# V1.net
KiCad netlist of a schematic drawn in EAGLE
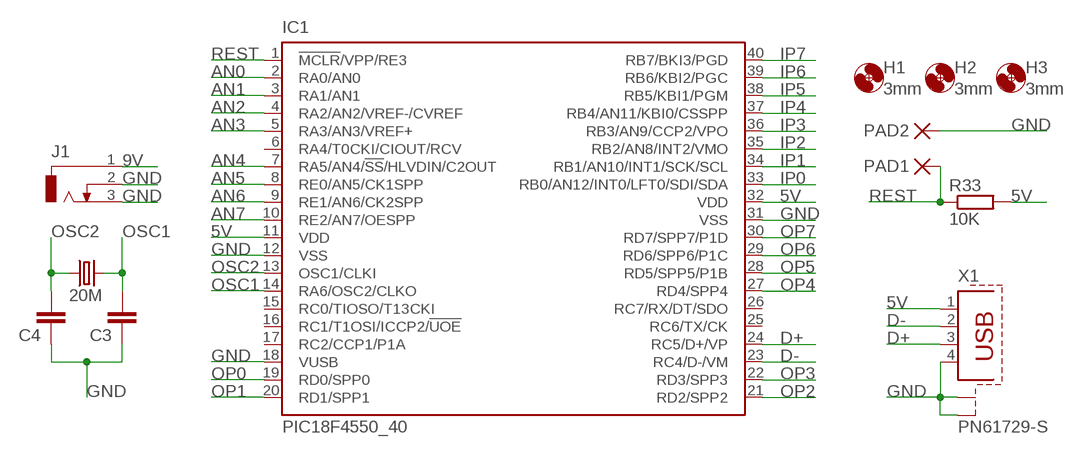
[diagram p0: schematic, sheet 1]
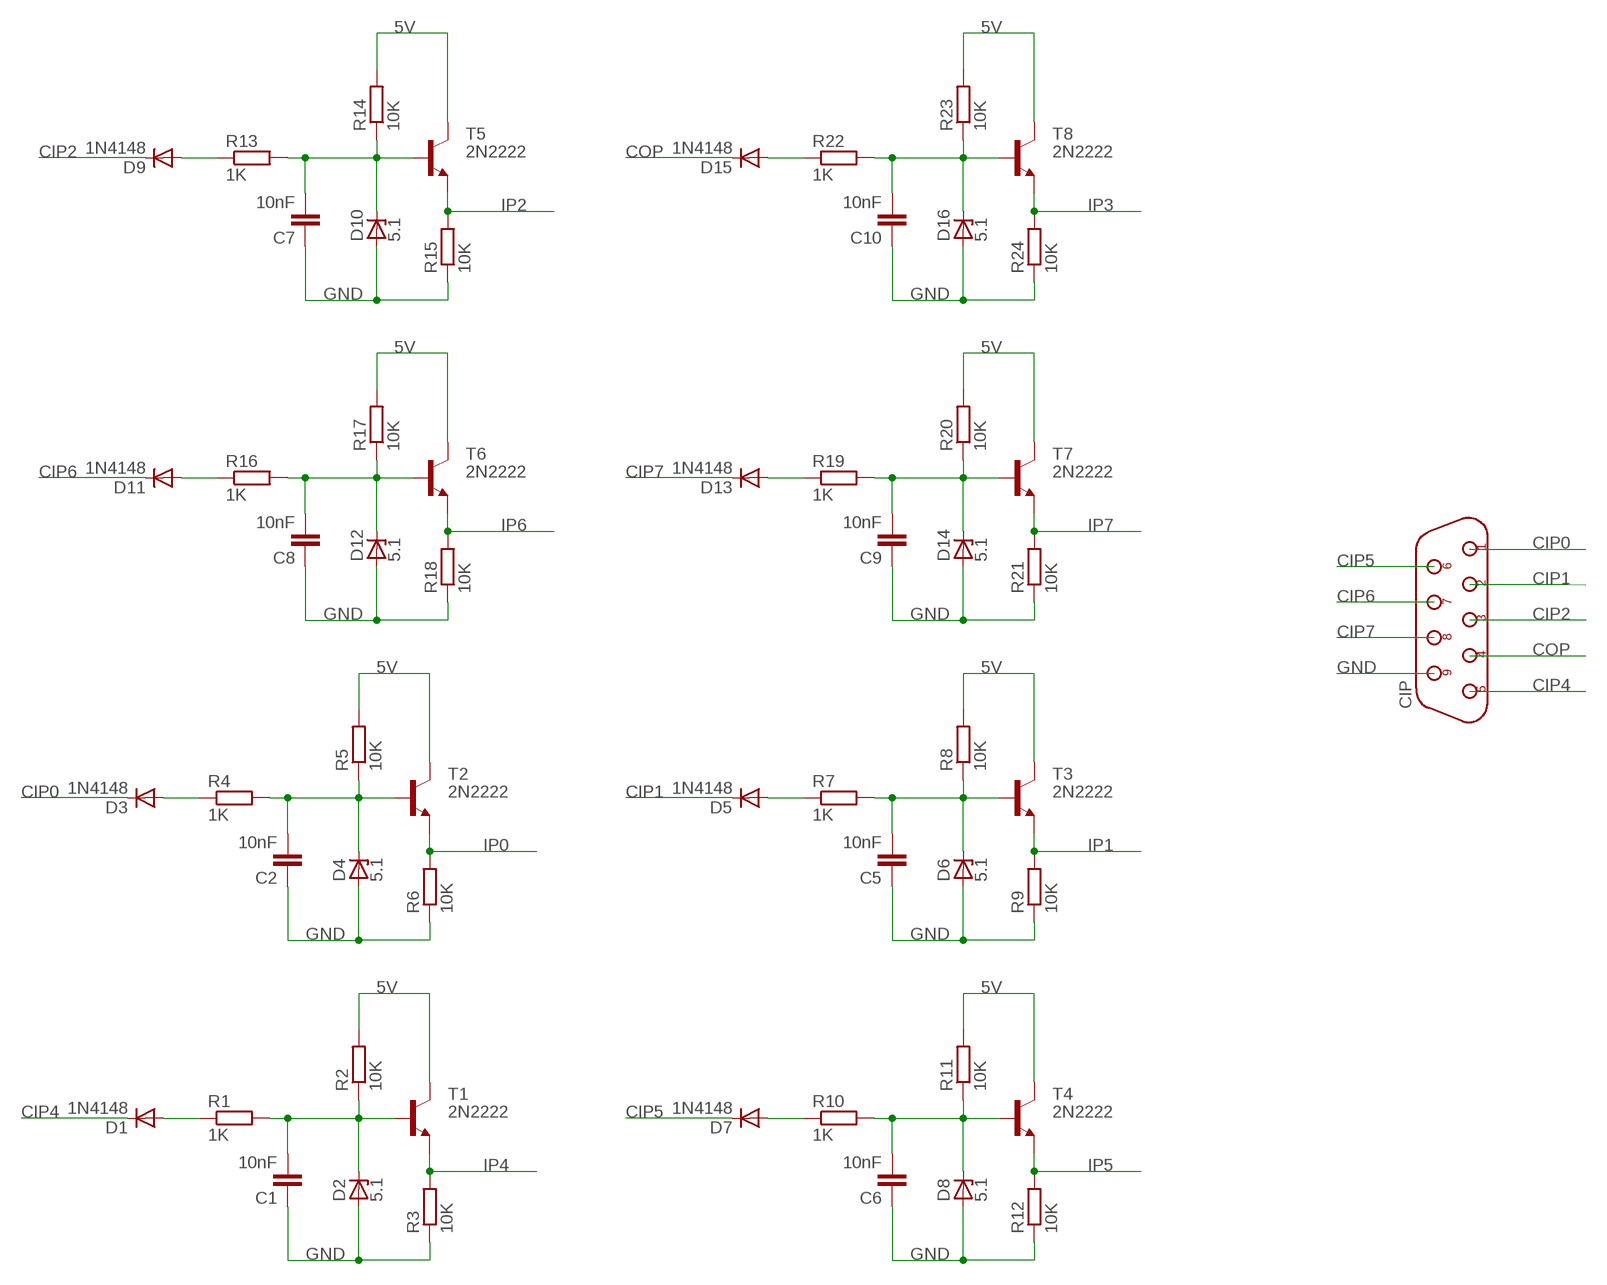
[diagram p1: schematic, sheet 2]
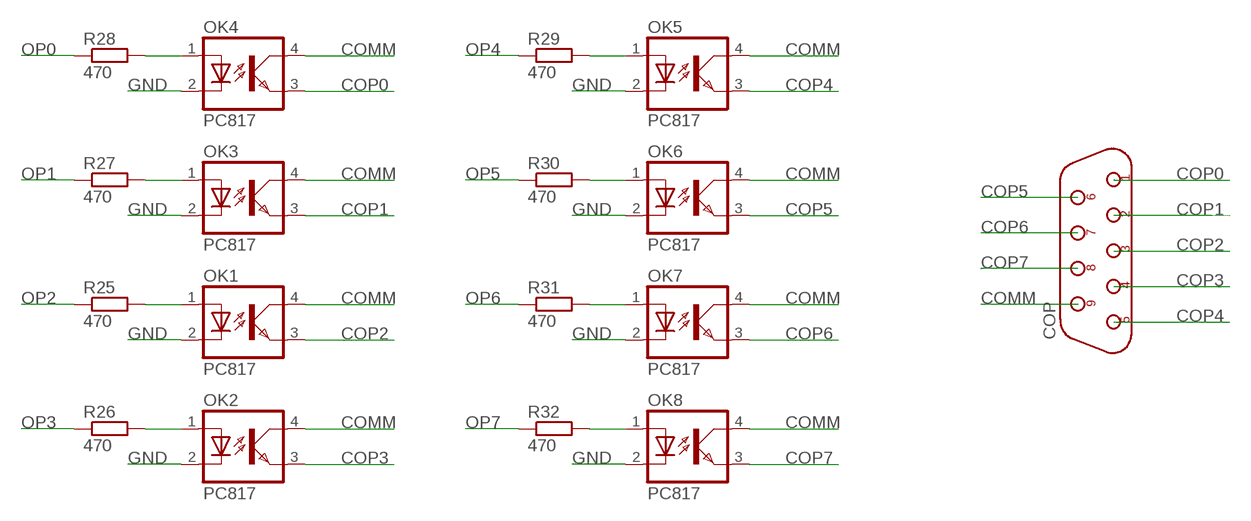
[diagram p2: schematic, sheet 3]
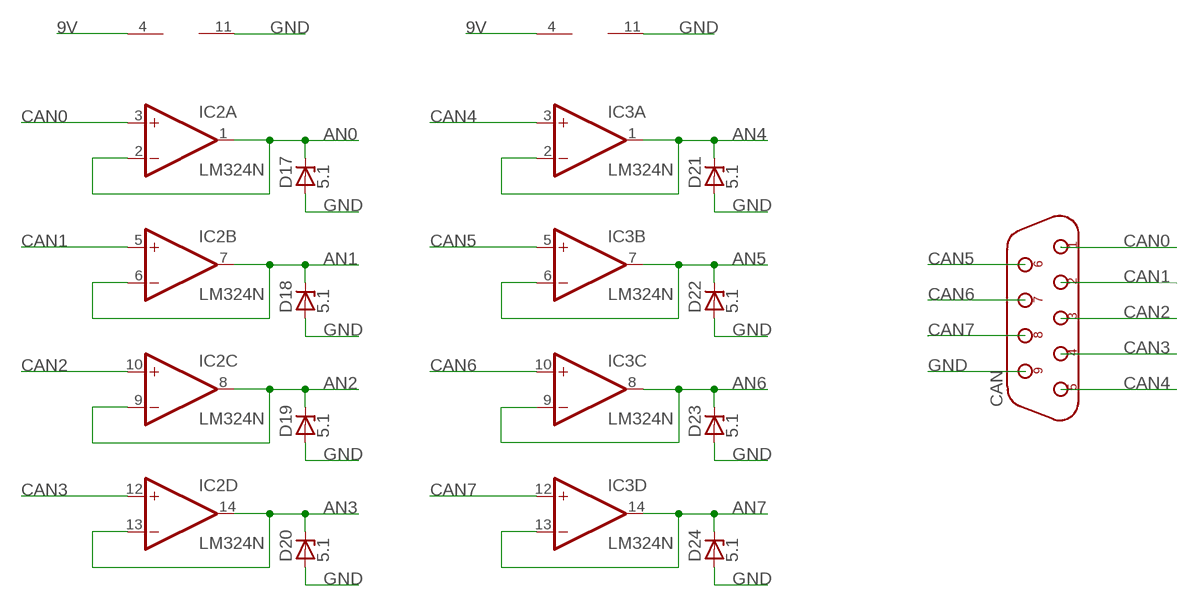
[diagram p3: schematic, sheet 4]

(export (version "E")
  (design (tool "Eeschema 10.0.6"))
  (components
    (comp (ref "COP")
      (value "DB9F/90")
      (footprint "eagle-import:D-09F_90")
      (libsource (lib "eagle-import") (part "DB9F/90"))
    )
    (comp (ref "OK1")
      (value "PC817")
      (footprint "eagle-import:DIL04")
      (fields (field (name "MPN") "PC817X4J000F"))
      (libsource (lib "eagle-import") (part "PC817"))
    )
    (comp (ref "OK2")
      (value "PC817")
      (footprint "eagle-import:DIL04")
      (fields (field (name "MPN") "PC817X4J000F"))
      (libsource (lib "eagle-import") (part "PC817"))
    )
    (comp (ref "OK3")
      (value "PC817")
      (footprint "eagle-import:DIL04")
      (fields (field (name "MPN") "PC817X4J000F"))
      (libsource (lib "eagle-import") (part "PC817"))
    )
    (comp (ref "OK4")
      (value "PC817")
      (footprint "eagle-import:DIL04")
      (fields (field (name "MPN") "PC817X4J000F"))
      (libsource (lib "eagle-import") (part "PC817"))
    )
    (comp (ref "OK5")
      (value "PC817")
      (footprint "eagle-import:DIL04")
      (fields (field (name "MPN") "PC817X4J000F"))
      (libsource (lib "eagle-import") (part "PC817"))
    )
    (comp (ref "OK6")
      (value "PC817")
      (footprint "eagle-import:DIL04")
      (fields (field (name "MPN") "PC817X4J000F"))
      (libsource (lib "eagle-import") (part "PC817"))
    )
    (comp (ref "OK7")
      (value "PC817")
      (footprint "eagle-import:DIL04")
      (fields (field (name "MPN") "PC817X4J000F"))
      (libsource (lib "eagle-import") (part "PC817"))
    )
    (comp (ref "OK8")
      (value "PC817")
      (footprint "eagle-import:DIL04")
      (fields (field (name "MPN") "PC817X4J000F"))
      (libsource (lib "eagle-import") (part "PC817"))
    )
    (comp (ref "R25")
      (value "470")
      (footprint "eagle-import:0207_10")
      (libsource (lib "eagle-import") (part "R-EU_0207/10"))
    )
    (comp (ref "R26")
      (value "470")
      (footprint "eagle-import:0207_10")
      (libsource (lib "eagle-import") (part "R-EU_0207/10"))
    )
    (comp (ref "R27")
      (value "470")
      (footprint "eagle-import:0207_10")
      (libsource (lib "eagle-import") (part "R-EU_0207/10"))
    )
    (comp (ref "R28")
      (value "470")
      (footprint "eagle-import:0207_10")
      (libsource (lib "eagle-import") (part "R-EU_0207/10"))
    )
    (comp (ref "R29")
      (value "470")
      (footprint "eagle-import:0207_10")
      (libsource (lib "eagle-import") (part "R-EU_0207/10"))
    )
    (comp (ref "R30")
      (value "470")
      (footprint "eagle-import:0207_10")
      (libsource (lib "eagle-import") (part "R-EU_0207/10"))
    )
    (comp (ref "R31")
      (value "470")
      (footprint "eagle-import:0207_10")
      (libsource (lib "eagle-import") (part "R-EU_0207/10"))
    )
    (comp (ref "R32")
      (value "470")
      (footprint "eagle-import:0207_10")
      (libsource (lib "eagle-import") (part "R-EU_0207/10"))
    )
    (comp (ref "20M")
      (value "CRYSTALHC18U-V")
      (footprint "eagle-import:HC18U-V")
      (libsource (lib "eagle-import") (part "CRYSTALHC18U-V"))
    )
    (comp (ref "C3")
      (value "C5/2.5")
      (footprint "eagle-import:C5B2.5")
      (libsource (lib "eagle-import") (part "C5/2.5"))
    )
    (comp (ref "C4")
      (value "C5/2.5")
      (footprint "eagle-import:C5B2.5")
      (libsource (lib "eagle-import") (part "C5/2.5"))
    )
    (comp (ref "H1")
      (value "3mm")
      (footprint "eagle-import:3,0")
      (libsource (lib "eagle-import") (part "MOUNT-HOLE3.0"))
    )
    (comp (ref "H2")
      (value "3mm")
      (footprint "eagle-import:3,0")
      (libsource (lib "eagle-import") (part "MOUNT-HOLE3.0"))
    )
    (comp (ref "H3")
      (value "3mm")
      (footprint "eagle-import:3,0")
      (libsource (lib "eagle-import") (part "MOUNT-HOLE3.0"))
    )
    (comp (ref "IC1")
      (value "PIC18F4550_40")
      (footprint "eagle-import:DIL40")
      (fields (field (name "MF") "MICROCHIP") (field (name "MPN") "PIC18F4550-I/P"))
      (libsource (lib "eagle-import") (part "PIC18F4_40550"))
    )
    (comp (ref "J1")
      (value "DCJ0303")
      (footprint "eagle-import:DCJ0303")
      (libsource (lib "eagle-import") (part "DCJ0303"))
    )
    (comp (ref "PAD1")
      (value "PAD-0320")
      (footprint "eagle-import:0320")
      (libsource (lib "eagle-import") (part "PAD-0320"))
    )
    (comp (ref "PAD2")
      (value "PAD-0320")
      (footprint "eagle-import:0320")
      (libsource (lib "eagle-import") (part "PAD-0320"))
    )
    (comp (ref "R33")
      (value "10K")
      (footprint "eagle-import:0207_10")
      (libsource (lib "eagle-import") (part "R-EU_0207/10"))
    )
    (comp (ref "X1")
      (value "PN61729-S")
      (footprint "eagle-import:PN61729-S")
      (libsource (lib "eagle-import") (part "PN61729-S"))
    )
    (comp (ref "CAN")
      (value "DB9F/90")
      (footprint "eagle-import:D-09F_90")
      (libsource (lib "eagle-import") (part "DB9F/90"))
    )
    (comp (ref "D17")
      (value "5.1")
      (footprint "eagle-import:ZDIO-10")
      (libsource (lib "eagle-import") (part "ZENER-DIODEZD-10"))
    )
    (comp (ref "D18")
      (value "5.1")
      (footprint "eagle-import:ZDIO-10")
      (libsource (lib "eagle-import") (part "ZENER-DIODEZD-10"))
    )
    (comp (ref "D19")
      (value "5.1")
      (footprint "eagle-import:ZDIO-10")
      (libsource (lib "eagle-import") (part "ZENER-DIODEZD-10"))
    )
    (comp (ref "D20")
      (value "5.1")
      (footprint "eagle-import:ZDIO-10")
      (libsource (lib "eagle-import") (part "ZENER-DIODEZD-10"))
    )
    (comp (ref "D21")
      (value "5.1")
      (footprint "eagle-import:ZDIO-10")
      (libsource (lib "eagle-import") (part "ZENER-DIODEZD-10"))
    )
    (comp (ref "D22")
      (value "5.1")
      (footprint "eagle-import:ZDIO-10")
      (libsource (lib "eagle-import") (part "ZENER-DIODEZD-10"))
    )
    (comp (ref "D23")
      (value "5.1")
      (footprint "eagle-import:ZDIO-10")
      (libsource (lib "eagle-import") (part "ZENER-DIODEZD-10"))
    )
    (comp (ref "D24")
      (value "5.1")
      (footprint "eagle-import:ZDIO-10")
      (libsource (lib "eagle-import") (part "ZENER-DIODEZD-10"))
    )
    (comp (ref "IC2")
      (value "LM324N")
      (footprint "eagle-import:DIL14")
      (libsource (lib "eagle-import") (part "LM324N"))
    )
    (comp (ref "IC3")
      (value "LM324N")
      (footprint "eagle-import:DIL14")
      (libsource (lib "eagle-import") (part "LM324N"))
    )
    (comp (ref "C1")
      (value "10nF")
      (footprint "eagle-import:C5B2.5")
      (libsource (lib "eagle-import") (part "C5/2.5"))
    )
    (comp (ref "C2")
      (value "10nF")
      (footprint "eagle-import:C5B2.5")
      (libsource (lib "eagle-import") (part "C5/2.5"))
    )
    (comp (ref "C5")
      (value "10nF")
      (footprint "eagle-import:C5B2.5")
      (libsource (lib "eagle-import") (part "C5/2.5"))
    )
    (comp (ref "C6")
      (value "10nF")
      (footprint "eagle-import:C5B2.5")
      (libsource (lib "eagle-import") (part "C5/2.5"))
    )
    (comp (ref "C7")
      (value "10nF")
      (footprint "eagle-import:C5B2.5")
      (libsource (lib "eagle-import") (part "C5/2.5"))
    )
    (comp (ref "C8")
      (value "10nF")
      (footprint "eagle-import:C5B2.5")
      (libsource (lib "eagle-import") (part "C5/2.5"))
    )
    (comp (ref "C9")
      (value "10nF")
      (footprint "eagle-import:C5B2.5")
      (libsource (lib "eagle-import") (part "C5/2.5"))
    )
    (comp (ref "C10")
      (value "10nF")
      (footprint "eagle-import:C5B2.5")
      (libsource (lib "eagle-import") (part "C5/2.5"))
    )
    (comp (ref "CIP")
      (value "DB9F/90")
      (footprint "eagle-import:D-09F_90")
      (libsource (lib "eagle-import") (part "DB9F/90"))
    )
    (comp (ref "D1")
      (value "1N4148")
      (footprint "eagle-import:DO35-10")
      (libsource (lib "eagle-import") (part "1N4148"))
    )
    (comp (ref "D2")
      (value "5.1")
      (footprint "eagle-import:ZDIO-10")
      (libsource (lib "eagle-import") (part "diode_210_ZENER-DIODEZD-10"))
    )
    (comp (ref "D3")
      (value "1N4148")
      (footprint "eagle-import:DO35-10")
      (libsource (lib "eagle-import") (part "1N4148"))
    )
    (comp (ref "D4")
      (value "5.1")
      (footprint "eagle-import:ZDIO-10")
      (libsource (lib "eagle-import") (part "diode_210_ZENER-DIODEZD-10"))
    )
    (comp (ref "D5")
      (value "1N4148")
      (footprint "eagle-import:DO35-10")
      (libsource (lib "eagle-import") (part "1N4148"))
    )
    (comp (ref "D6")
      (value "5.1")
      (footprint "eagle-import:ZDIO-10")
      (libsource (lib "eagle-import") (part "diode_210_ZENER-DIODEZD-10"))
    )
    (comp (ref "D7")
      (value "1N4148")
      (footprint "eagle-import:DO35-10")
      (libsource (lib "eagle-import") (part "1N4148"))
    )
    (comp (ref "D8")
      (value "5.1")
      (footprint "eagle-import:ZDIO-10")
      (libsource (lib "eagle-import") (part "diode_210_ZENER-DIODEZD-10"))
    )
    (comp (ref "D9")
      (value "1N4148")
      (footprint "eagle-import:DO35-10")
      (libsource (lib "eagle-import") (part "1N4148"))
    )
    (comp (ref "D10")
      (value "5.1")
      (footprint "eagle-import:ZDIO-10")
      (libsource (lib "eagle-import") (part "diode_210_ZENER-DIODEZD-10"))
    )
    (comp (ref "D11")
      (value "1N4148")
      (footprint "eagle-import:DO35-10")
      (libsource (lib "eagle-import") (part "1N4148"))
    )
    (comp (ref "D12")
      (value "5.1")
      (footprint "eagle-import:ZDIO-10")
      (libsource (lib "eagle-import") (part "diode_210_ZENER-DIODEZD-10"))
    )
    (comp (ref "D13")
      (value "1N4148")
      (footprint "eagle-import:DO35-10")
      (libsource (lib "eagle-import") (part "1N4148"))
    )
    (comp (ref "D14")
      (value "5.1")
      (footprint "eagle-import:ZDIO-10")
      (libsource (lib "eagle-import") (part "diode_210_ZENER-DIODEZD-10"))
    )
    (comp (ref "D15")
      (value "1N4148")
      (footprint "eagle-import:DO35-10")
      (libsource (lib "eagle-import") (part "1N4148"))
    )
    (comp (ref "D16")
      (value "5.1")
      (footprint "eagle-import:ZDIO-10")
      (libsource (lib "eagle-import") (part "diode_210_ZENER-DIODEZD-10"))
    )
    (comp (ref "R1")
      (value "1K")
      (footprint "eagle-import:0207_10")
      (libsource (lib "eagle-import") (part "R-EU_0207/10"))
    )
    (comp (ref "R2")
      (value "10K")
      (footprint "eagle-import:0207_10")
      (libsource (lib "eagle-import") (part "R-EU_0207/10"))
    )
    (comp (ref "R3")
      (value "10K")
      (footprint "eagle-import:0207_10")
      (libsource (lib "eagle-import") (part "R-EU_0207/10"))
    )
    (comp (ref "R4")
      (value "1K")
      (footprint "eagle-import:0207_10")
      (libsource (lib "eagle-import") (part "R-EU_0207/10"))
    )
    (comp (ref "R5")
      (value "10K")
      (footprint "eagle-import:0207_10")
      (libsource (lib "eagle-import") (part "R-EU_0207/10"))
    )
    (comp (ref "R6")
      (value "10K")
      (footprint "eagle-import:0207_10")
      (libsource (lib "eagle-import") (part "R-EU_0207/10"))
    )
    (comp (ref "R7")
      (value "1K")
      (footprint "eagle-import:0207_10")
      (libsource (lib "eagle-import") (part "R-EU_0207/10"))
    )
    (comp (ref "R8")
      (value "10K")
      (footprint "eagle-import:0207_10")
      (libsource (lib "eagle-import") (part "R-EU_0207/10"))
    )
    (comp (ref "R9")
      (value "10K")
      (footprint "eagle-import:0207_10")
      (libsource (lib "eagle-import") (part "R-EU_0207/10"))
    )
    (comp (ref "R10")
      (value "1K")
      (footprint "eagle-import:0207_10")
      (libsource (lib "eagle-import") (part "R-EU_0207/10"))
    )
    (comp (ref "R11")
      (value "10K")
      (footprint "eagle-import:0207_10")
      (libsource (lib "eagle-import") (part "R-EU_0207/10"))
    )
    (comp (ref "R12")
      (value "10K")
      (footprint "eagle-import:0207_10")
      (libsource (lib "eagle-import") (part "R-EU_0207/10"))
    )
    (comp (ref "R13")
      (value "1K")
      (footprint "eagle-import:0207_10")
      (libsource (lib "eagle-import") (part "R-EU_0207/10"))
    )
    (comp (ref "R14")
      (value "10K")
      (footprint "eagle-import:0207_10")
      (libsource (lib "eagle-import") (part "R-EU_0207/10"))
    )
    (comp (ref "R15")
      (value "10K")
      (footprint "eagle-import:0207_10")
      (libsource (lib "eagle-import") (part "R-EU_0207/10"))
    )
    (comp (ref "R16")
      (value "1K")
      (footprint "eagle-import:0207_10")
      (libsource (lib "eagle-import") (part "R-EU_0207/10"))
    )
    (comp (ref "R17")
      (value "10K")
      (footprint "eagle-import:0207_10")
      (libsource (lib "eagle-import") (part "R-EU_0207/10"))
    )
    (comp (ref "R18")
      (value "10K")
      (footprint "eagle-import:0207_10")
      (libsource (lib "eagle-import") (part "R-EU_0207/10"))
    )
    (comp (ref "R19")
      (value "1K")
      (footprint "eagle-import:0207_10")
      (libsource (lib "eagle-import") (part "R-EU_0207/10"))
    )
    (comp (ref "R20")
      (value "10K")
      (footprint "eagle-import:0207_10")
      (libsource (lib "eagle-import") (part "R-EU_0207/10"))
    )
    (comp (ref "R21")
      (value "10K")
      (footprint "eagle-import:0207_10")
      (libsource (lib "eagle-import") (part "R-EU_0207/10"))
    )
    (comp (ref "R22")
      (value "1K")
      (footprint "eagle-import:0207_10")
      (libsource (lib "eagle-import") (part "R-EU_0207/10"))
    )
    (comp (ref "R23")
      (value "10K")
      (footprint "eagle-import:0207_10")
      (libsource (lib "eagle-import") (part "R-EU_0207/10"))
    )
    (comp (ref "R24")
      (value "10K")
      (footprint "eagle-import:0207_10")
      (libsource (lib "eagle-import") (part "R-EU_0207/10"))
    )
    (comp (ref "T1")
      (value "2N2222")
      (footprint "eagle-import:TO92-EBC-OVAL")
      (libsource (lib "eagle-import") (part "2N2222"))
    )
    (comp (ref "T2")
      (value "2N2222")
      (footprint "eagle-import:TO92-EBC-OVAL")
      (libsource (lib "eagle-import") (part "2N2222"))
    )
    (comp (ref "T3")
      (value "2N2222")
      (footprint "eagle-import:TO92-EBC-OVAL")
      (libsource (lib "eagle-import") (part "2N2222"))
    )
    (comp (ref "T4")
      (value "2N2222")
      (footprint "eagle-import:TO92-EBC-OVAL")
      (libsource (lib "eagle-import") (part "2N2222"))
    )
    (comp (ref "T5")
      (value "2N2222")
      (footprint "eagle-import:TO92-EBC-OVAL")
      (libsource (lib "eagle-import") (part "2N2222"))
    )
    (comp (ref "T6")
      (value "2N2222")
      (footprint "eagle-import:TO92-EBC-OVAL")
      (libsource (lib "eagle-import") (part "2N2222"))
    )
    (comp (ref "T7")
      (value "2N2222")
      (footprint "eagle-import:TO92-EBC-OVAL")
      (libsource (lib "eagle-import") (part "2N2222"))
    )
    (comp (ref "T8")
      (value "2N2222")
      (footprint "eagle-import:TO92-EBC-OVAL")
      (libsource (lib "eagle-import") (part "2N2222"))
    )
  )
  (nets
    (net (code "1") (name "5V") (class "Default")
      (node (ref "IC1") (pin "11") (pinfunction "VDD_11") (pintype "power_in"))
      (node (ref "IC1") (pin "32") (pinfunction "VDD_32") (pintype "power_in"))
      (node (ref "R11") (pin "2") (pinfunction "2_2") (pintype "passive"))
      (node (ref "R14") (pin "2") (pinfunction "2_2") (pintype "passive"))
      (node (ref "R17") (pin "2") (pinfunction "2_2") (pintype "passive"))
      (node (ref "R2") (pin "2") (pinfunction "2_2") (pintype "passive"))
      (node (ref "R20") (pin "2") (pinfunction "2_2") (pintype "passive"))
      (node (ref "R23") (pin "2") (pinfunction "2_2") (pintype "passive"))
      (node (ref "R33") (pin "2") (pinfunction "2_2") (pintype "passive"))
      (node (ref "R5") (pin "2") (pinfunction "2_2") (pintype "passive"))
      (node (ref "R8") (pin "2") (pinfunction "2_2") (pintype "passive"))
      (node (ref "T1") (pin "C") (pinfunction "C_C") (pintype "passive"))
      (node (ref "T2") (pin "C") (pinfunction "C_C") (pintype "passive"))
      (node (ref "T3") (pin "C") (pinfunction "C_C") (pintype "passive"))
      (node (ref "T4") (pin "C") (pinfunction "C_C") (pintype "passive"))
      (node (ref "T5") (pin "C") (pinfunction "C_C") (pintype "passive"))
      (node (ref "T6") (pin "C") (pinfunction "C_C") (pintype "passive"))
      (node (ref "T7") (pin "C") (pinfunction "C_C") (pintype "passive"))
      (node (ref "T8") (pin "C") (pinfunction "C_C") (pintype "passive"))
      (node (ref "X1") (pin "1") (pinfunction "1_1") (pintype "passive"))
    )
    (net (code "2") (name "9V") (class "Default")
      (node (ref "IC2") (pin "4") (pinfunction "V+_4") (pintype "power_in"))
      (node (ref "IC3") (pin "4") (pinfunction "V+_4") (pintype "power_in"))
      (node (ref "J1") (pin "1") (pinfunction "1_1") (pintype "passive"))
    )
    (net (code "3") (name "AN0") (class "Default")
      (node (ref "D17") (pin "C") (pinfunction "C_C") (pintype "passive"))
      (node (ref "IC1") (pin "2") (pinfunction "RA0/AN0_2") (pintype "bidirectional"))
      (node (ref "IC2") (pin "1") (pinfunction "OUT_1") (pintype "output"))
      (node (ref "IC2") (pin "2") (pinfunction "-IN_2") (pintype "input"))
    )
    (net (code "4") (name "AN1") (class "Default")
      (node (ref "D18") (pin "C") (pinfunction "C_C") (pintype "passive"))
      (node (ref "IC1") (pin "3") (pinfunction "RA1/AN1_3") (pintype "bidirectional"))
      (node (ref "IC2") (pin "6") (pinfunction "-IN_6") (pintype "input"))
      (node (ref "IC2") (pin "7") (pinfunction "OUT_7") (pintype "output"))
    )
    (net (code "5") (name "AN2") (class "Default")
      (node (ref "D19") (pin "C") (pinfunction "C_C") (pintype "passive"))
      (node (ref "IC1") (pin "4") (pinfunction "RA2/AN2/VREF-/CVREF_4") (pintype "bidirectional"))
      (node (ref "IC2") (pin "8") (pinfunction "OUT_8") (pintype "output"))
      (node (ref "IC2") (pin "9") (pinfunction "-IN_9") (pintype "input"))
    )
    (net (code "6") (name "AN3") (class "Default")
      (node (ref "D20") (pin "C") (pinfunction "C_C") (pintype "passive"))
      (node (ref "IC1") (pin "5") (pinfunction "RA3/AN3/VREF+_5") (pintype "bidirectional"))
      (node (ref "IC2") (pin "13") (pinfunction "-IN_13") (pintype "input"))
      (node (ref "IC2") (pin "14") (pinfunction "OUT_14") (pintype "output"))
    )
    (net (code "7") (name "AN4") (class "Default")
      (node (ref "D21") (pin "C") (pinfunction "C_C") (pintype "passive"))
      (node (ref "IC1") (pin "7") (pinfunction "RA5/AN4/~{SS}/HLVDIN/C2OUT_7") (pintype "bidirectional"))
      (node (ref "IC3") (pin "1") (pinfunction "OUT_1") (pintype "output"))
      (node (ref "IC3") (pin "2") (pinfunction "-IN_2") (pintype "input"))
    )
    (net (code "8") (name "AN5") (class "Default")
      (node (ref "D22") (pin "C") (pinfunction "C_C") (pintype "passive"))
      (node (ref "IC1") (pin "8") (pinfunction "RE0/AN5/CK1SPP_8") (pintype "bidirectional"))
      (node (ref "IC3") (pin "6") (pinfunction "-IN_6") (pintype "input"))
      (node (ref "IC3") (pin "7") (pinfunction "OUT_7") (pintype "output"))
    )
    (net (code "9") (name "AN6") (class "Default")
      (node (ref "D23") (pin "C") (pinfunction "C_C") (pintype "passive"))
      (node (ref "IC1") (pin "9") (pinfunction "RE1/AN6/CK2SPP_9") (pintype "bidirectional"))
      (node (ref "IC3") (pin "8") (pinfunction "OUT_8") (pintype "output"))
      (node (ref "IC3") (pin "9") (pinfunction "-IN_9") (pintype "input"))
    )
    (net (code "10") (name "AN7") (class "Default")
      (node (ref "D24") (pin "C") (pinfunction "C_C") (pintype "passive"))
      (node (ref "IC1") (pin "10") (pinfunction "RE2/AN7/OESPP_10") (pintype "bidirectional"))
      (node (ref "IC3") (pin "13") (pinfunction "-IN_13") (pintype "input"))
      (node (ref "IC3") (pin "14") (pinfunction "OUT_14") (pintype "output"))
    )
    (net (code "11") (name "CAN0") (class "Default")
      (node (ref "CAN") (pin "1") (pinfunction "1_1") (pintype "passive"))
      (node (ref "IC2") (pin "3") (pinfunction "+IN_3") (pintype "input"))
    )
    (net (code "12") (name "CAN1") (class "Default")
      (node (ref "CAN") (pin "2") (pinfunction "2_2") (pintype "passive"))
      (node (ref "IC2") (pin "5") (pinfunction "+IN_5") (pintype "input"))
    )
    (net (code "13") (name "CAN2") (class "Default")
      (node (ref "CAN") (pin "3") (pinfunction "3_3") (pintype "passive"))
      (node (ref "IC2") (pin "10") (pinfunction "+IN_10") (pintype "input"))
    )
    (net (code "14") (name "CAN3") (class "Default")
      (node (ref "CAN") (pin "4") (pinfunction "4_4") (pintype "passive"))
      (node (ref "IC2") (pin "12") (pinfunction "+IN_12") (pintype "input"))
    )
    (net (code "15") (name "CAN4") (class "Default")
      (node (ref "CAN") (pin "5") (pinfunction "5_5") (pintype "passive"))
      (node (ref "IC3") (pin "3") (pinfunction "+IN_3") (pintype "input"))
    )
    (net (code "16") (name "CAN5") (class "Default")
      (node (ref "CAN") (pin "6") (pinfunction "6_6") (pintype "passive"))
      (node (ref "IC3") (pin "5") (pinfunction "+IN_5") (pintype "input"))
    )
    (net (code "17") (name "CAN6") (class "Default")
      (node (ref "CAN") (pin "7") (pinfunction "7_7") (pintype "passive"))
      (node (ref "IC3") (pin "10") (pinfunction "+IN_10") (pintype "input"))
    )
    (net (code "18") (name "CAN7") (class "Default")
      (node (ref "CAN") (pin "8") (pinfunction "8_8") (pintype "passive"))
      (node (ref "IC3") (pin "12") (pinfunction "+IN_12") (pintype "input"))
    )
    (net (code "19") (name "CIP0") (class "Default")
      (node (ref "CIP") (pin "1") (pinfunction "1_1") (pintype "passive"))
      (node (ref "D3") (pin "C") (pinfunction "C_C") (pintype "passive"))
    )
    (net (code "20") (name "CIP1") (class "Default")
      (node (ref "CIP") (pin "2") (pinfunction "2_2") (pintype "passive"))
      (node (ref "D5") (pin "C") (pinfunction "C_C") (pintype "passive"))
    )
    (net (code "21") (name "CIP2") (class "Default")
      (node (ref "CIP") (pin "3") (pinfunction "3_3") (pintype "passive"))
      (node (ref "D9") (pin "C") (pinfunction "C_C") (pintype "passive"))
    )
    (net (code "22") (name "CIP4") (class "Default")
      (node (ref "CIP") (pin "5") (pinfunction "5_5") (pintype "passive"))
      (node (ref "D1") (pin "C") (pinfunction "C_C") (pintype "passive"))
    )
    (net (code "23") (name "CIP5") (class "Default")
      (node (ref "CIP") (pin "6") (pinfunction "6_6") (pintype "passive"))
      (node (ref "D7") (pin "C") (pinfunction "C_C") (pintype "passive"))
    )
    (net (code "24") (name "CIP6") (class "Default")
      (node (ref "CIP") (pin "7") (pinfunction "7_7") (pintype "passive"))
      (node (ref "D11") (pin "C") (pinfunction "C_C") (pintype "passive"))
    )
    (net (code "25") (name "CIP7") (class "Default")
      (node (ref "CIP") (pin "8") (pinfunction "8_8") (pintype "passive"))
      (node (ref "D13") (pin "C") (pinfunction "C_C") (pintype "passive"))
    )
    (net (code "26") (name "COMM") (class "Default")
      (node (ref "COP") (pin "9") (pinfunction "9_9") (pintype "passive"))
      (node (ref "OK1") (pin "4") (pinfunction "COL_4") (pintype "passive"))
      (node (ref "OK2") (pin "4") (pinfunction "COL_4") (pintype "passive"))
      (node (ref "OK3") (pin "4") (pinfunction "COL_4") (pintype "passive"))
      (node (ref "OK4") (pin "4") (pinfunction "COL_4") (pintype "passive"))
      (node (ref "OK5") (pin "4") (pinfunction "COL_4") (pintype "passive"))
      (node (ref "OK6") (pin "4") (pinfunction "COL_4") (pintype "passive"))
      (node (ref "OK7") (pin "4") (pinfunction "COL_4") (pintype "passive"))
      (node (ref "OK8") (pin "4") (pinfunction "COL_4") (pintype "passive"))
    )
    (net (code "27") (name "COP") (class "Default")
      (node (ref "CIP") (pin "4") (pinfunction "4_4") (pintype "passive"))
      (node (ref "D15") (pin "C") (pinfunction "C_C") (pintype "passive"))
    )
    (net (code "28") (name "COP0") (class "Default")
      (node (ref "COP") (pin "1") (pinfunction "1_1") (pintype "passive"))
      (node (ref "OK4") (pin "3") (pinfunction "EMIT_3") (pintype "passive"))
    )
    (net (code "29") (name "COP1") (class "Default")
      (node (ref "COP") (pin "2") (pinfunction "2_2") (pintype "passive"))
      (node (ref "OK3") (pin "3") (pinfunction "EMIT_3") (pintype "passive"))
    )
    (net (code "30") (name "COP2") (class "Default")
      (node (ref "COP") (pin "3") (pinfunction "3_3") (pintype "passive"))
      (node (ref "OK1") (pin "3") (pinfunction "EMIT_3") (pintype "passive"))
    )
    (net (code "31") (name "COP3") (class "Default")
      (node (ref "COP") (pin "4") (pinfunction "4_4") (pintype "passive"))
      (node (ref "OK2") (pin "3") (pinfunction "EMIT_3") (pintype "passive"))
    )
    (net (code "32") (name "COP4") (class "Default")
      (node (ref "COP") (pin "5") (pinfunction "5_5") (pintype "passive"))
      (node (ref "OK5") (pin "3") (pinfunction "EMIT_3") (pintype "passive"))
    )
    (net (code "33") (name "COP5") (class "Default")
      (node (ref "COP") (pin "6") (pinfunction "6_6") (pintype "passive"))
      (node (ref "OK6") (pin "3") (pinfunction "EMIT_3") (pintype "passive"))
    )
    (net (code "34") (name "COP6") (class "Default")
      (node (ref "COP") (pin "7") (pinfunction "7_7") (pintype "passive"))
      (node (ref "OK7") (pin "3") (pinfunction "EMIT_3") (pintype "passive"))
    )
    (net (code "35") (name "COP7") (class "Default")
      (node (ref "COP") (pin "8") (pinfunction "8_8") (pintype "passive"))
      (node (ref "OK8") (pin "3") (pinfunction "EMIT_3") (pintype "passive"))
    )
    (net (code "36") (name "D+") (class "Default")
      (node (ref "IC1") (pin "24") (pinfunction "RC5/D+/VP_24") (pintype "bidirectional"))
      (node (ref "X1") (pin "3") (pinfunction "3_3") (pintype "passive"))
    )
    (net (code "37") (name "D-") (class "Default")
      (node (ref "IC1") (pin "23") (pinfunction "RC4/D-/VM_23") (pintype "bidirectional"))
      (node (ref "X1") (pin "2") (pinfunction "2_2") (pintype "passive"))
    )
    (net (code "38") (name "GND") (class "Default")
      (node (ref "C1") (pin "1") (pinfunction "1_1") (pintype "passive"))
      (node (ref "C10") (pin "1") (pinfunction "1_1") (pintype "passive"))
      (node (ref "C2") (pin "1") (pinfunction "1_1") (pintype "passive"))
      (node (ref "C3") (pin "1") (pinfunction "1_1") (pintype "passive"))
      (node (ref "C4") (pin "1") (pinfunction "1_1") (pintype "passive"))
      (node (ref "C5") (pin "1") (pinfunction "1_1") (pintype "passive"))
      (node (ref "C6") (pin "1") (pinfunction "1_1") (pintype "passive"))
      (node (ref "C7") (pin "1") (pinfunction "1_1") (pintype "passive"))
      (node (ref "C8") (pin "1") (pinfunction "1_1") (pintype "passive"))
      (node (ref "C9") (pin "1") (pinfunction "1_1") (pintype "passive"))
      (node (ref "CAN") (pin "9") (pinfunction "9_9") (pintype "passive"))
      (node (ref "CIP") (pin "9") (pinfunction "9_9") (pintype "passive"))
      (node (ref "D10") (pin "A") (pinfunction "A_A") (pintype "passive"))
      (node (ref "D12") (pin "A") (pinfunction "A_A") (pintype "passive"))
      (node (ref "D14") (pin "A") (pinfunction "A_A") (pintype "passive"))
      (node (ref "D16") (pin "A") (pinfunction "A_A") (pintype "passive"))
      (node (ref "D17") (pin "A") (pinfunction "A_A") (pintype "passive"))
      (node (ref "D18") (pin "A") (pinfunction "A_A") (pintype "passive"))
      (node (ref "D19") (pin "A") (pinfunction "A_A") (pintype "passive"))
      (node (ref "D2") (pin "A") (pinfunction "A_A") (pintype "passive"))
      (node (ref "D20") (pin "A") (pinfunction "A_A") (pintype "passive"))
      (node (ref "D21") (pin "A") (pinfunction "A_A") (pintype "passive"))
      (node (ref "D22") (pin "A") (pinfunction "A_A") (pintype "passive"))
      (node (ref "D23") (pin "A") (pinfunction "A_A") (pintype "passive"))
      (node (ref "D24") (pin "A") (pinfunction "A_A") (pintype "passive"))
      (node (ref "D4") (pin "A") (pinfunction "A_A") (pintype "passive"))
      (node (ref "D6") (pin "A") (pinfunction "A_A") (pintype "passive"))
      (node (ref "D8") (pin "A") (pinfunction "A_A") (pintype "passive"))
      (node (ref "IC1") (pin "12") (pinfunction "VSS_12") (pintype "power_in"))
      (node (ref "IC1") (pin "18") (pinfunction "VUSB_18") (pintype "bidirectional"))
      (node (ref "IC1") (pin "31") (pinfunction "VSS_31") (pintype "power_in"))
      (node (ref "IC2") (pin "11") (pinfunction "V-_11") (pintype "power_in"))
      (node (ref "IC3") (pin "11") (pinfunction "V-_11") (pintype "power_in"))
      (node (ref "J1") (pin "2") (pinfunction "2_2") (pintype "passive"))
      (node (ref "J1") (pin "3") (pinfunction "3_3") (pintype "passive"))
      (node (ref "OK1") (pin "2") (pinfunction "C_2") (pintype "passive"))
      (node (ref "OK2") (pin "2") (pinfunction "C_2") (pintype "passive"))
      (node (ref "OK3") (pin "2") (pinfunction "C_2") (pintype "passive"))
      (node (ref "OK4") (pin "2") (pinfunction "C_2") (pintype "passive"))
      (node (ref "OK5") (pin "2") (pinfunction "C_2") (pintype "passive"))
      (node (ref "OK6") (pin "2") (pinfunction "C_2") (pintype "passive"))
      (node (ref "OK7") (pin "2") (pinfunction "C_2") (pintype "passive"))
      (node (ref "OK8") (pin "2") (pinfunction "C_2") (pintype "passive"))
      (node (ref "PAD2") (pin "P$1") (pinfunction "P_P$1") (pintype "passive"))
      (node (ref "R12") (pin "1") (pinfunction "1_1") (pintype "passive"))
      (node (ref "R15") (pin "1") (pinfunction "1_1") (pintype "passive"))
      (node (ref "R18") (pin "1") (pinfunction "1_1") (pintype "passive"))
      (node (ref "R21") (pin "1") (pinfunction "1_1") (pintype "passive"))
      (node (ref "R24") (pin "1") (pinfunction "1_1") (pintype "passive"))
      (node (ref "R3") (pin "1") (pinfunction "1_1") (pintype "passive"))
      (node (ref "R6") (pin "1") (pinfunction "1_1") (pintype "passive"))
      (node (ref "R9") (pin "1") (pinfunction "1_1") (pintype "passive"))
      (node (ref "X1") (pin "4") (pinfunction "4_4") (pintype "passive"))
      (node (ref "X1") (pin "S1") (pinfunction "S1_S1") (pintype "passive"))
      (node (ref "X1") (pin "S2") (pinfunction "S2_S2") (pintype "passive"))
    )
    (net (code "39") (name "IP0") (class "Default")
      (node (ref "IC1") (pin "33") (pinfunction "RB0/AN12/INT0/LFT0/SDI/SDA_33") (pintype "bidirectional"))
      (node (ref "R6") (pin "2") (pinfunction "2_2") (pintype "passive"))
      (node (ref "T2") (pin "E") (pinfunction "E_E") (pintype "passive"))
    )
    (net (code "40") (name "IP1") (class "Default")
      (node (ref "IC1") (pin "34") (pinfunction "RB1/AN10/INT1/SCK/SCL_34") (pintype "bidirectional"))
      (node (ref "R9") (pin "2") (pinfunction "2_2") (pintype "passive"))
      (node (ref "T3") (pin "E") (pinfunction "E_E") (pintype "passive"))
    )
    (net (code "41") (name "IP2") (class "Default")
      (node (ref "IC1") (pin "35") (pinfunction "RB2/AN8/INT2/VMO_35") (pintype "bidirectional"))
      (node (ref "R15") (pin "2") (pinfunction "2_2") (pintype "passive"))
      (node (ref "T5") (pin "E") (pinfunction "E_E") (pintype "passive"))
    )
    (net (code "42") (name "IP3") (class "Default")
      (node (ref "IC1") (pin "36") (pinfunction "RB3/AN9/CCP2/VPO_36") (pintype "bidirectional"))
      (node (ref "R24") (pin "2") (pinfunction "2_2") (pintype "passive"))
      (node (ref "T8") (pin "E") (pinfunction "E_E") (pintype "passive"))
    )
    (net (code "43") (name "IP4") (class "Default")
      (node (ref "IC1") (pin "37") (pinfunction "RB4/AN11/KBI0/CSSPP_37") (pintype "bidirectional"))
      (node (ref "R3") (pin "2") (pinfunction "2_2") (pintype "passive"))
      (node (ref "T1") (pin "E") (pinfunction "E_E") (pintype "passive"))
    )
    (net (code "44") (name "IP5") (class "Default")
      (node (ref "IC1") (pin "38") (pinfunction "RB5/KBI1/PGM_38") (pintype "bidirectional"))
      (node (ref "R12") (pin "2") (pinfunction "2_2") (pintype "passive"))
      (node (ref "T4") (pin "E") (pinfunction "E_E") (pintype "passive"))
    )
    (net (code "45") (name "IP6") (class "Default")
      (node (ref "IC1") (pin "39") (pinfunction "RB6/KBI2/PGC_39") (pintype "bidirectional"))
      (node (ref "R18") (pin "2") (pinfunction "2_2") (pintype "passive"))
      (node (ref "T6") (pin "E") (pinfunction "E_E") (pintype "passive"))
    )
    (net (code "46") (name "IP7") (class "Default")
      (node (ref "IC1") (pin "40") (pinfunction "RB7/BKI3/PGD_40") (pintype "bidirectional"))
      (node (ref "R21") (pin "2") (pinfunction "2_2") (pintype "passive"))
      (node (ref "T7") (pin "E") (pinfunction "E_E") (pintype "passive"))
    )
    (net (code "47") (name "Net-(C1-Pad2)") (class "Default")
      (node (ref "C1") (pin "2") (pinfunction "2_2") (pintype "passive"))
      (node (ref "D2") (pin "C") (pinfunction "C_C") (pintype "passive"))
      (node (ref "R1") (pin "2") (pinfunction "2_2") (pintype "passive"))
      (node (ref "R2") (pin "1") (pinfunction "1_1") (pintype "passive"))
      (node (ref "T1") (pin "B") (pinfunction "B_B") (pintype "passive"))
    )
    (net (code "48") (name "Net-(C2-Pad2)") (class "Default")
      (node (ref "C2") (pin "2") (pinfunction "2_2") (pintype "passive"))
      (node (ref "D4") (pin "C") (pinfunction "C_C") (pintype "passive"))
      (node (ref "R4") (pin "2") (pinfunction "2_2") (pintype "passive"))
      (node (ref "R5") (pin "1") (pinfunction "1_1") (pintype "passive"))
      (node (ref "T2") (pin "B") (pinfunction "B_B") (pintype "passive"))
    )
    (net (code "49") (name "Net-(C5-Pad2)") (class "Default")
      (node (ref "C5") (pin "2") (pinfunction "2_2") (pintype "passive"))
      (node (ref "D6") (pin "C") (pinfunction "C_C") (pintype "passive"))
      (node (ref "R7") (pin "2") (pinfunction "2_2") (pintype "passive"))
      (node (ref "R8") (pin "1") (pinfunction "1_1") (pintype "passive"))
      (node (ref "T3") (pin "B") (pinfunction "B_B") (pintype "passive"))
    )
    (net (code "50") (name "Net-(C6-Pad2)") (class "Default")
      (node (ref "C6") (pin "2") (pinfunction "2_2") (pintype "passive"))
      (node (ref "D8") (pin "C") (pinfunction "C_C") (pintype "passive"))
      (node (ref "R10") (pin "2") (pinfunction "2_2") (pintype "passive"))
      (node (ref "R11") (pin "1") (pinfunction "1_1") (pintype "passive"))
      (node (ref "T4") (pin "B") (pinfunction "B_B") (pintype "passive"))
    )
    (net (code "51") (name "Net-(C7-Pad2)") (class "Default")
      (node (ref "C7") (pin "2") (pinfunction "2_2") (pintype "passive"))
      (node (ref "D10") (pin "C") (pinfunction "C_C") (pintype "passive"))
      (node (ref "R13") (pin "2") (pinfunction "2_2") (pintype "passive"))
      (node (ref "R14") (pin "1") (pinfunction "1_1") (pintype "passive"))
      (node (ref "T5") (pin "B") (pinfunction "B_B") (pintype "passive"))
    )
    (net (code "52") (name "Net-(C8-Pad2)") (class "Default")
      (node (ref "C8") (pin "2") (pinfunction "2_2") (pintype "passive"))
      (node (ref "D12") (pin "C") (pinfunction "C_C") (pintype "passive"))
      (node (ref "R16") (pin "2") (pinfunction "2_2") (pintype "passive"))
      (node (ref "R17") (pin "1") (pinfunction "1_1") (pintype "passive"))
      (node (ref "T6") (pin "B") (pinfunction "B_B") (pintype "passive"))
    )
    (net (code "53") (name "Net-(C9-Pad2)") (class "Default")
      (node (ref "C9") (pin "2") (pinfunction "2_2") (pintype "passive"))
      (node (ref "D14") (pin "C") (pinfunction "C_C") (pintype "passive"))
      (node (ref "R19") (pin "2") (pinfunction "2_2") (pintype "passive"))
      (node (ref "R20") (pin "1") (pinfunction "1_1") (pintype "passive"))
      (node (ref "T7") (pin "B") (pinfunction "B_B") (pintype "passive"))
    )
    (net (code "54") (name "Net-(C10-Pad2)") (class "Default")
      (node (ref "C10") (pin "2") (pinfunction "2_2") (pintype "passive"))
      (node (ref "D16") (pin "C") (pinfunction "C_C") (pintype "passive"))
      (node (ref "R22") (pin "2") (pinfunction "2_2") (pintype "passive"))
      (node (ref "R23") (pin "1") (pinfunction "1_1") (pintype "passive"))
      (node (ref "T8") (pin "B") (pinfunction "B_B") (pintype "passive"))
    )
    (net (code "55") (name "Net-(D1-PadA)") (class "Default")
      (node (ref "D1") (pin "A") (pinfunction "A_A") (pintype "passive"))
      (node (ref "R1") (pin "1") (pinfunction "1_1") (pintype "passive"))
    )
    (net (code "56") (name "Net-(D3-PadA)") (class "Default")
      (node (ref "D3") (pin "A") (pinfunction "A_A") (pintype "passive"))
      (node (ref "R4") (pin "1") (pinfunction "1_1") (pintype "passive"))
    )
    (net (code "57") (name "Net-(D5-PadA)") (class "Default")
      (node (ref "D5") (pin "A") (pinfunction "A_A") (pintype "passive"))
      (node (ref "R7") (pin "1") (pinfunction "1_1") (pintype "passive"))
    )
    (net (code "58") (name "Net-(D7-PadA)") (class "Default")
      (node (ref "D7") (pin "A") (pinfunction "A_A") (pintype "passive"))
      (node (ref "R10") (pin "1") (pinfunction "1_1") (pintype "passive"))
    )
    (net (code "59") (name "Net-(D9-PadA)") (class "Default")
      (node (ref "D9") (pin "A") (pinfunction "A_A") (pintype "passive"))
      (node (ref "R13") (pin "1") (pinfunction "1_1") (pintype "passive"))
    )
    (net (code "60") (name "Net-(D11-PadA)") (class "Default")
      (node (ref "D11") (pin "A") (pinfunction "A_A") (pintype "passive"))
      (node (ref "R16") (pin "1") (pinfunction "1_1") (pintype "passive"))
    )
    (net (code "61") (name "Net-(D13-PadA)") (class "Default")
      (node (ref "D13") (pin "A") (pinfunction "A_A") (pintype "passive"))
      (node (ref "R19") (pin "1") (pinfunction "1_1") (pintype "passive"))
    )
    (net (code "62") (name "Net-(D15-PadA)") (class "Default")
      (node (ref "D15") (pin "A") (pinfunction "A_A") (pintype "passive"))
      (node (ref "R22") (pin "1") (pinfunction "1_1") (pintype "passive"))
    )
    (net (code "63") (name "Net-(OK1-A)") (class "Default")
      (node (ref "OK1") (pin "1") (pinfunction "A_1") (pintype "passive"))
      (node (ref "R25") (pin "2") (pinfunction "2_2") (pintype "passive"))
    )
    (net (code "64") (name "Net-(OK2-A)") (class "Default")
      (node (ref "OK2") (pin "1") (pinfunction "A_1") (pintype "passive"))
      (node (ref "R26") (pin "2") (pinfunction "2_2") (pintype "passive"))
    )
    (net (code "65") (name "Net-(OK3-A)") (class "Default")
      (node (ref "OK3") (pin "1") (pinfunction "A_1") (pintype "passive"))
      (node (ref "R27") (pin "2") (pinfunction "2_2") (pintype "passive"))
    )
    (net (code "66") (name "Net-(OK4-A)") (class "Default")
      (node (ref "OK4") (pin "1") (pinfunction "A_1") (pintype "passive"))
      (node (ref "R28") (pin "2") (pinfunction "2_2") (pintype "passive"))
    )
    (net (code "67") (name "Net-(OK5-A)") (class "Default")
      (node (ref "OK5") (pin "1") (pinfunction "A_1") (pintype "passive"))
      (node (ref "R29") (pin "2") (pinfunction "2_2") (pintype "passive"))
    )
    (net (code "68") (name "Net-(OK6-A)") (class "Default")
      (node (ref "OK6") (pin "1") (pinfunction "A_1") (pintype "passive"))
      (node (ref "R30") (pin "2") (pinfunction "2_2") (pintype "passive"))
    )
    (net (code "69") (name "Net-(OK7-A)") (class "Default")
      (node (ref "OK7") (pin "1") (pinfunction "A_1") (pintype "passive"))
      (node (ref "R31") (pin "2") (pinfunction "2_2") (pintype "passive"))
    )
    (net (code "70") (name "Net-(OK8-A)") (class "Default")
      (node (ref "OK8") (pin "1") (pinfunction "A_1") (pintype "passive"))
      (node (ref "R32") (pin "2") (pinfunction "2_2") (pintype "passive"))
    )
    (net (code "71") (name "OP0") (class "Default")
      (node (ref "IC1") (pin "19") (pinfunction "RD0/SPP0_19") (pintype "bidirectional"))
      (node (ref "R28") (pin "1") (pinfunction "1_1") (pintype "passive"))
    )
    (net (code "72") (name "OP1") (class "Default")
      (node (ref "IC1") (pin "20") (pinfunction "RD1/SPP1_20") (pintype "bidirectional"))
      (node (ref "R27") (pin "1") (pinfunction "1_1") (pintype "passive"))
    )
    (net (code "73") (name "OP2") (class "Default")
      (node (ref "IC1") (pin "21") (pinfunction "RD2/SPP2_21") (pintype "bidirectional"))
      (node (ref "R25") (pin "1") (pinfunction "1_1") (pintype "passive"))
    )
    (net (code "74") (name "OP3") (class "Default")
      (node (ref "IC1") (pin "22") (pinfunction "RD3/SPP3_22") (pintype "bidirectional"))
      (node (ref "R26") (pin "1") (pinfunction "1_1") (pintype "passive"))
    )
    (net (code "75") (name "OP4") (class "Default")
      (node (ref "IC1") (pin "27") (pinfunction "RD4/SPP4_27") (pintype "bidirectional"))
      (node (ref "R29") (pin "1") (pinfunction "1_1") (pintype "passive"))
    )
    (net (code "76") (name "OP5") (class "Default")
      (node (ref "IC1") (pin "28") (pinfunction "RD5/SPP5/P1B_28") (pintype "bidirectional"))
      (node (ref "R30") (pin "1") (pinfunction "1_1") (pintype "passive"))
    )
    (net (code "77") (name "OP6") (class "Default")
      (node (ref "IC1") (pin "29") (pinfunction "RD6/SPP6/P1C_29") (pintype "bidirectional"))
      (node (ref "R31") (pin "1") (pinfunction "1_1") (pintype "passive"))
    )
    (net (code "78") (name "OP7") (class "Default")
      (node (ref "IC1") (pin "30") (pinfunction "RD7/SPP7/P1D_30") (pintype "bidirectional"))
      (node (ref "R32") (pin "1") (pinfunction "1_1") (pintype "passive"))
    )
    (net (code "79") (name "OSC1") (class "Default")
      (node (ref "20M") (pin "2") (pinfunction "2_2") (pintype "passive"))
      (node (ref "C3") (pin "2") (pinfunction "2_2") (pintype "passive"))
      (node (ref "IC1") (pin "14") (pinfunction "RA6/OSC2/CLKO_14") (pintype "output"))
    )
    (net (code "80") (name "OSC2") (class "Default")
      (node (ref "20M") (pin "1") (pinfunction "1_1") (pintype "passive"))
      (node (ref "C4") (pin "2") (pinfunction "2_2") (pintype "passive"))
      (node (ref "IC1") (pin "13") (pinfunction "OSC1/CLKI_13") (pintype "input"))
    )
    (net (code "81") (name "REST") (class "Default")
      (node (ref "IC1") (pin "1") (pinfunction "~{MCLR}/VPP/RE3_1") (pintype "input"))
      (node (ref "PAD1") (pin "P$1") (pinfunction "P_P$1") (pintype "passive"))
      (node (ref "R33") (pin "1") (pinfunction "1_1") (pintype "passive"))
    )
    (net (code "82") (name "unconnected-(IC1-RA4{slash}T0CKI{slash}CIOUT{slash}RCV-Pad6)") (class "Default")
      (node (ref "IC1") (pin "6") (pinfunction "RA4/T0CKI/CIOUT/RCV_6") (pintype "bidirectional"))
    )
    (net (code "83") (name "unconnected-(IC1-RC0{slash}TIOSO{slash}T13CKI-Pad15)") (class "Default")
      (node (ref "IC1") (pin "15") (pinfunction "RC0/TIOSO/T13CKI_15") (pintype "bidirectional"))
    )
    (net (code "84") (name "unconnected-(IC1-RC1{slash}T1OSI{slash}ICCP2{slash}~{UOE}-Pad16)") (class "Default")
      (node (ref "IC1") (pin "16") (pinfunction "RC1/T1OSI/ICCP2/~{UOE}_16") (pintype "bidirectional"))
    )
    (net (code "85") (name "unconnected-(IC1-RC2{slash}CCP1{slash}P1A-Pad17)") (class "Default")
      (node (ref "IC1") (pin "17") (pinfunction "RC2/CCP1/P1A_17") (pintype "bidirectional"))
    )
    (net (code "86") (name "unconnected-(IC1-RC6{slash}TX{slash}CK-Pad25)") (class "Default")
      (node (ref "IC1") (pin "25") (pinfunction "RC6/TX/CK_25") (pintype "bidirectional"))
    )
    (net (code "87") (name "unconnected-(IC1-RC7{slash}RX{slash}DT{slash}SDO-Pad26)") (class "Default")
      (node (ref "IC1") (pin "26") (pinfunction "RC7/RX/DT/SDO_26") (pintype "bidirectional"))
    )
  )
)
